# HEG_50mm_SENSOR.net
KiCad netlist of a schematic drawn in EAGLE
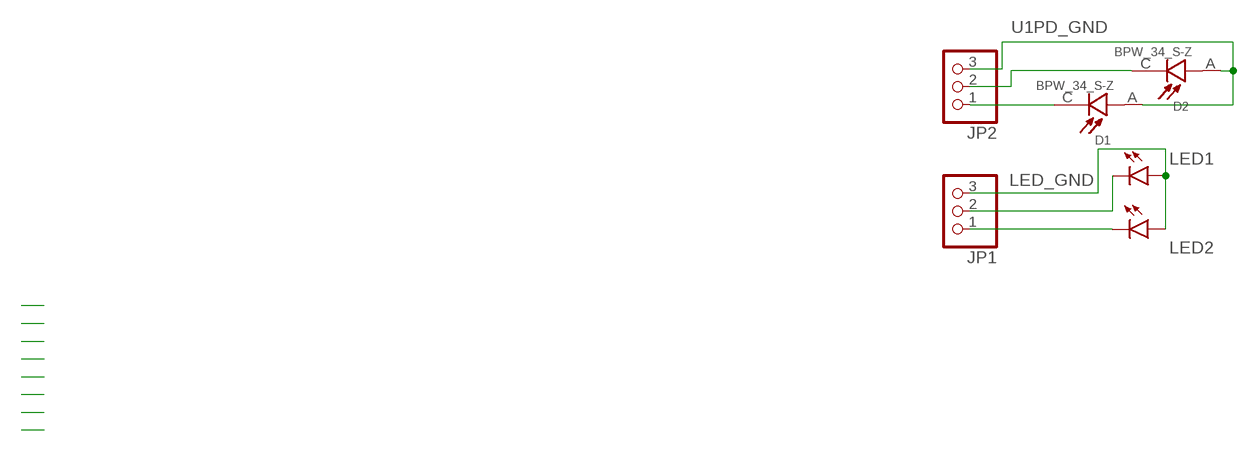
[diagram p0: schematic, sheet 1]

(export (version "E")
  (design (tool "Eeschema 10.0.6"))
  (components
    (comp (ref "D1")
      (value "BPW_34_S-Z")
      (footprint "eagle-import:DIO_BPW_34_S-Z")
      (fields
        (field (name "DIGI-KEY_PART_NUMBER") "475-2659-1-ND")
        (field (name "MF") "OSRAM Opto")
        (field (name "MP") "BPW 34 S-Z")
      )
      (libsource (lib "eagle-import") (part "BPW_34_S-Z"))
    )
    (comp (ref "D2")
      (value "BPW_34_S-Z")
      (footprint "eagle-import:DIO_BPW_34_S-Z")
      (fields
        (field (name "DIGI-KEY_PART_NUMBER") "475-2659-1-ND")
        (field (name "MF") "OSRAM Opto")
        (field (name "MP") "BPW 34 S-Z")
      )
      (libsource (lib "eagle-import") (part "BPW_34_S-Z"))
    )
    (comp (ref "JP1")
      (value "PINHD-1X3")
      (footprint "eagle-import:1X03")
      (libsource (lib "eagle-import") (part "PINHD-1X3"))
    )
    (comp (ref "JP2")
      (value "PINHD-1X3")
      (footprint "eagle-import:1X03")
      (libsource (lib "eagle-import") (part "PINHD-1X3"))
    )
    (comp (ref "LED1")
      (value "LEDCHIPLED_1206")
      (footprint "eagle-import:CHIPLED_1206")
      (libsource (lib "eagle-import") (part "LEDCHIPLED_1206"))
    )
    (comp (ref "LED2")
      (value "LEDCHIPLED_1206")
      (footprint "eagle-import:CHIPLED_1206")
      (libsource (lib "eagle-import") (part "LEDCHIPLED_1206"))
    )
  )
  (nets
    (net (code "1") (name "/LED_GND") (class "Default")
      (node (ref "JP1") (pin "3") (pinfunction "3_3") (pintype "passive"))
      (node (ref "LED1") (pin "A") (pinfunction "A_A") (pintype "passive"))
      (node (ref "LED2") (pin "A") (pinfunction "A_A") (pintype "passive"))
    )
    (net (code "2") (name "/U1PD_GND") (class "Default")
      (node (ref "D1") (pin "A") (pinfunction "A_A") (pintype "passive"))
      (node (ref "D2") (pin "A") (pinfunction "A_A") (pintype "passive"))
      (node (ref "JP2") (pin "3") (pinfunction "3_3") (pintype "passive"))
    )
    (net (code "3") (name "Net-(D1-PadC)") (class "Default")
      (node (ref "D1") (pin "C") (pinfunction "C_C") (pintype "passive"))
      (node (ref "JP2") (pin "1") (pinfunction "1_1") (pintype "passive"))
    )
    (net (code "4") (name "Net-(D2-PadC)") (class "Default")
      (node (ref "D2") (pin "C") (pinfunction "C_C") (pintype "passive"))
      (node (ref "JP2") (pin "2") (pinfunction "2_2") (pintype "passive"))
    )
    (net (code "5") (name "Net-(JP1-Pad1)") (class "Default")
      (node (ref "JP1") (pin "1") (pinfunction "1_1") (pintype "passive"))
      (node (ref "LED2") (pin "C") (pinfunction "C_C") (pintype "passive"))
    )
    (net (code "6") (name "Net-(JP1-Pad2)") (class "Default")
      (node (ref "JP1") (pin "2") (pinfunction "2_2") (pintype "passive"))
      (node (ref "LED1") (pin "C") (pinfunction "C_C") (pintype "passive"))
    )
  )
)
